# Geiger_counter_HV_section.net
KiCad netlist of a schematic drawn in EAGLE
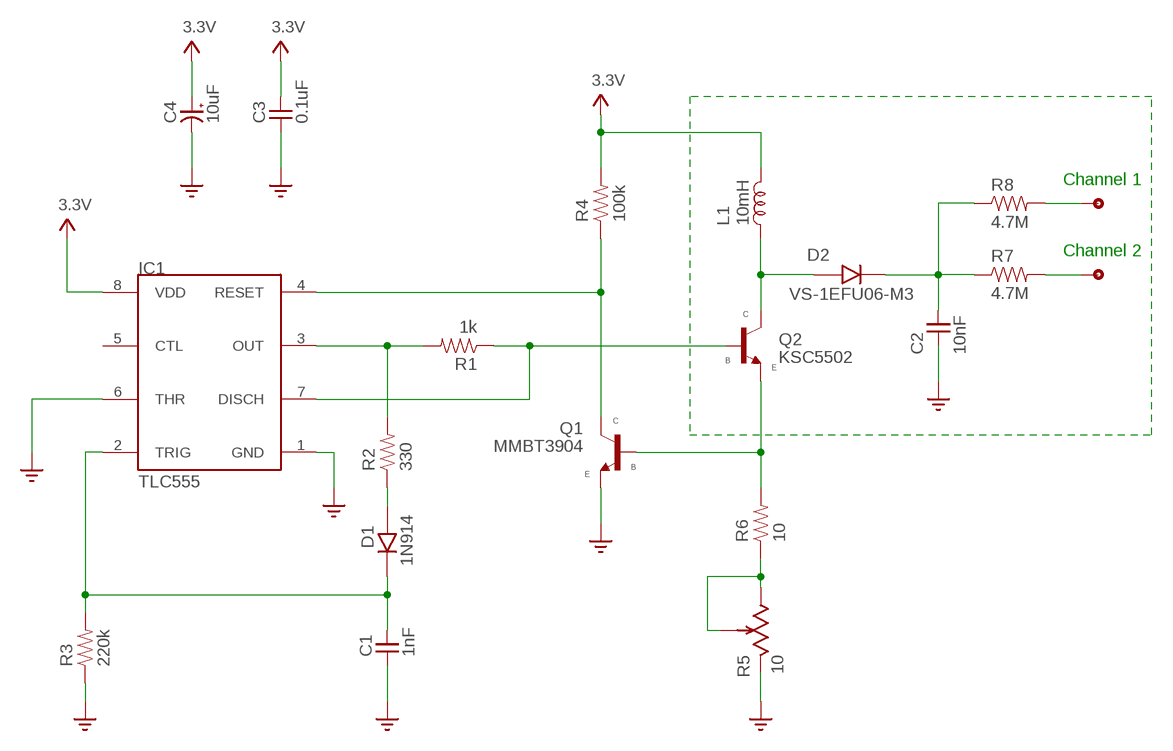
[diagram p0: schematic, sheet 1]

(export (version "E")
  (design (tool "Eeschema 10.0.6"))
  (components
    (comp (ref "C1")
      (value "1nF")
      (footprint "eagle-import:0805")
      (libsource (lib "eagle-import") (part "CAPACITOR0805"))
    )
    (comp (ref "C2")
      (value "10nF")
      (footprint "eagle-import:1206")
      (libsource (lib "eagle-import") (part "CAPACITOR1206"))
    )
    (comp (ref "C3")
      (value "0.1uF")
      (footprint "eagle-import:0805")
      (libsource (lib "eagle-import") (part "CAPACITOR0805"))
    )
    (comp (ref "C4")
      (value "10uF")
      (footprint "eagle-import:1206")
      (libsource (lib "eagle-import") (part "CAPACITOR+"))
    )
    (comp (ref "D1")
      (value "1N914")
      (footprint "eagle-import:0805")
      (libsource (lib "eagle-import") (part "DIODE0805"))
    )
    (comp (ref "D2")
      (value "VS-1EFU06-M3")
      (footprint "eagle-import:DO-219AB")
      (libsource (lib "eagle-import") (part "DIODE"))
    )
    (comp (ref "IC1")
      (value "TLC555")
      (footprint "eagle-import:SOIC8")
      (libsource (lib "eagle-import") (part "TLC555SOIC-8"))
    )
    (comp (ref "L1")
      (value "10mH")
      (footprint "eagle-import:1200LRS")
      (libsource (lib "eagle-import") (part "INDUCTOR1200LRS"))
    )
    (comp (ref "Q1")
      (value "MMBT3904")
      (footprint "eagle-import:SOT-23A")
      (libsource (lib "eagle-import") (part "MMBT3904"))
    )
    (comp (ref "Q2")
      (value "KSC5502")
      (footprint "eagle-import:TO-252")
      (libsource (lib "eagle-import") (part "KSC5502"))
    )
    (comp (ref "R1")
      (value "1k")
      (footprint "eagle-import:0805")
      (libsource (lib "eagle-import") (part "RESISTOR0805SMD"))
    )
    (comp (ref "R2")
      (value "330")
      (footprint "eagle-import:0805")
      (libsource (lib "eagle-import") (part "RESISTOR0805SMD"))
    )
    (comp (ref "R3")
      (value "220k")
      (footprint "eagle-import:0805")
      (libsource (lib "eagle-import") (part "RESISTOR0805SMD"))
    )
    (comp (ref "R4")
      (value "100k")
      (footprint "eagle-import:0805")
      (libsource (lib "eagle-import") (part "RESISTOR0805SMD"))
    )
    (comp (ref "R5")
      (value "10")
      (footprint "eagle-import:3362P")
      (libsource (lib "eagle-import") (part "TRIM_3362P"))
    )
    (comp (ref "R6")
      (value "10")
      (footprint "eagle-import:1206")
      (libsource (lib "eagle-import") (part "RESISTOR1206SMD"))
    )
    (comp (ref "R7")
      (value "4.7M")
      (footprint "eagle-import:1206")
      (libsource (lib "eagle-import") (part "RESISTOR1206SMD"))
    )
    (comp (ref "R8")
      (value "4.7M")
      (footprint "eagle-import:1206")
      (libsource (lib "eagle-import") (part "RESISTOR1206SMD"))
    )
    (comp (ref "TP1") (value "TP") (footprint "eagle-import:TP") (libsource (lib "eagle-import") (part "TP")))
    (comp (ref "TP2") (value "TP") (footprint "eagle-import:TP") (libsource (lib "eagle-import") (part "TP")))
  )
  (nets
    (net (code "1") (name "3.3V") (class "Default")
      (node (ref "C3") (pin "2") (pinfunction "2_2") (pintype "passive"))
      (node (ref "C4") (pin "1") (pinfunction "1_1") (pintype "passive"))
      (node (ref "IC1") (pin "8") (pinfunction "VDD_8") (pintype "bidirectional"))
      (node (ref "L1") (pin "P3") (pinfunction "2_P3") (pintype "bidirectional"))
      (node (ref "R4") (pin "2") (pinfunction "2_2") (pintype "passive"))
    )
    (net (code "2") (name "DGND") (class "Default")
      (node (ref "C1") (pin "1") (pinfunction "1_1") (pintype "passive"))
      (node (ref "C2") (pin "1") (pinfunction "1_1") (pintype "passive"))
      (node (ref "C3") (pin "1") (pinfunction "1_1") (pintype "passive"))
      (node (ref "C4") (pin "2") (pinfunction "2_2") (pintype "passive"))
      (node (ref "IC1") (pin "1") (pinfunction "GND_1") (pintype "bidirectional"))
      (node (ref "IC1") (pin "6") (pinfunction "THR_6") (pintype "bidirectional"))
      (node (ref "Q1") (pin "3") (pinfunction "E_3") (pintype "passive"))
      (node (ref "R3") (pin "1") (pinfunction "1_1") (pintype "passive"))
      (node (ref "R5") (pin "P$3") (pinfunction "P3_P$3") (pintype "bidirectional"))
    )
    (net (code "3") (name "Net-(D1-A)") (class "Default")
      (node (ref "D1") (pin "1") (pinfunction "A_1") (pintype "bidirectional"))
      (node (ref "R2") (pin "1") (pinfunction "1_1") (pintype "passive"))
    )
    (net (code "4") (name "Net-(D1-K)") (class "Default")
      (node (ref "C1") (pin "2") (pinfunction "2_2") (pintype "passive"))
      (node (ref "D1") (pin "2") (pinfunction "K_2") (pintype "bidirectional"))
      (node (ref "IC1") (pin "2") (pinfunction "TRIG_2") (pintype "bidirectional"))
      (node (ref "R3") (pin "2") (pinfunction "2_2") (pintype "passive"))
    )
    (net (code "5") (name "Net-(D2-A)") (class "Default")
      (node (ref "D2") (pin "P$1") (pinfunction "A_P$1") (pintype "bidirectional"))
      (node (ref "L1") (pin "P1") (pinfunction "1_P1") (pintype "bidirectional"))
      (node (ref "Q2") (pin "P$3") (pinfunction "C_P$3") (pintype "passive"))
    )
    (net (code "6") (name "Net-(D2-K)") (class "Default")
      (node (ref "C2") (pin "2") (pinfunction "2_2") (pintype "passive"))
      (node (ref "D2") (pin "P$2") (pinfunction "K_P$2") (pintype "bidirectional"))
      (node (ref "R7") (pin "1") (pinfunction "1_1") (pintype "passive"))
      (node (ref "R8") (pin "1") (pinfunction "1_1") (pintype "passive"))
    )
    (net (code "7") (name "Net-(IC1-DISCH)") (class "Default")
      (node (ref "IC1") (pin "7") (pinfunction "DISCH_7") (pintype "bidirectional"))
      (node (ref "Q2") (pin "P$1") (pinfunction "B_P$1") (pintype "passive"))
      (node (ref "R1") (pin "1") (pinfunction "1_1") (pintype "passive"))
    )
    (net (code "8") (name "Net-(IC1-OUT)") (class "Default")
      (node (ref "IC1") (pin "3") (pinfunction "OUT_3") (pintype "bidirectional"))
      (node (ref "R1") (pin "2") (pinfunction "2_2") (pintype "passive"))
      (node (ref "R2") (pin "2") (pinfunction "2_2") (pintype "passive"))
    )
    (net (code "9") (name "Net-(IC1-RESET)") (class "Default")
      (node (ref "IC1") (pin "4") (pinfunction "RESET_4") (pintype "bidirectional"))
      (node (ref "Q1") (pin "1") (pinfunction "C_1") (pintype "passive"))
      (node (ref "R4") (pin "1") (pinfunction "1_1") (pintype "passive"))
    )
    (net (code "10") (name "Net-(Q1-B)") (class "Default")
      (node (ref "Q1") (pin "2") (pinfunction "B_2") (pintype "passive"))
      (node (ref "Q2") (pin "P$2") (pinfunction "E_P$2") (pintype "passive"))
      (node (ref "R6") (pin "2") (pinfunction "2_2") (pintype "passive"))
    )
    (net (code "11") (name "Net-(R5-P1)") (class "Default")
      (node (ref "R5") (pin "P$1") (pinfunction "P1_P$1") (pintype "bidirectional"))
      (node (ref "R5") (pin "P$2") (pinfunction "WIPE_P$2") (pintype "bidirectional"))
      (node (ref "R6") (pin "1") (pinfunction "1_1") (pintype "passive"))
    )
    (net (code "12") (name "Net-(R7-Pad2)") (class "Default")
      (node (ref "R7") (pin "2") (pinfunction "2_2") (pintype "passive"))
      (node (ref "TP1") (pin "P$1") (pinfunction "P$1_P$1") (pintype "bidirectional"))
    )
    (net (code "13") (name "Net-(R8-Pad2)") (class "Default")
      (node (ref "R8") (pin "2") (pinfunction "2_2") (pintype "passive"))
      (node (ref "TP2") (pin "P$1") (pinfunction "P$1_P$1") (pintype "bidirectional"))
    )
    (net (code "14") (name "unconnected-(IC1-CTL-Pad5)") (class "Default")
      (node (ref "IC1") (pin "5") (pinfunction "CTL_5") (pintype "bidirectional"))
    )
  )
)
